# EPS_I2C-Repeater.net
KiCad netlist of a schematic drawn in Altium Designer
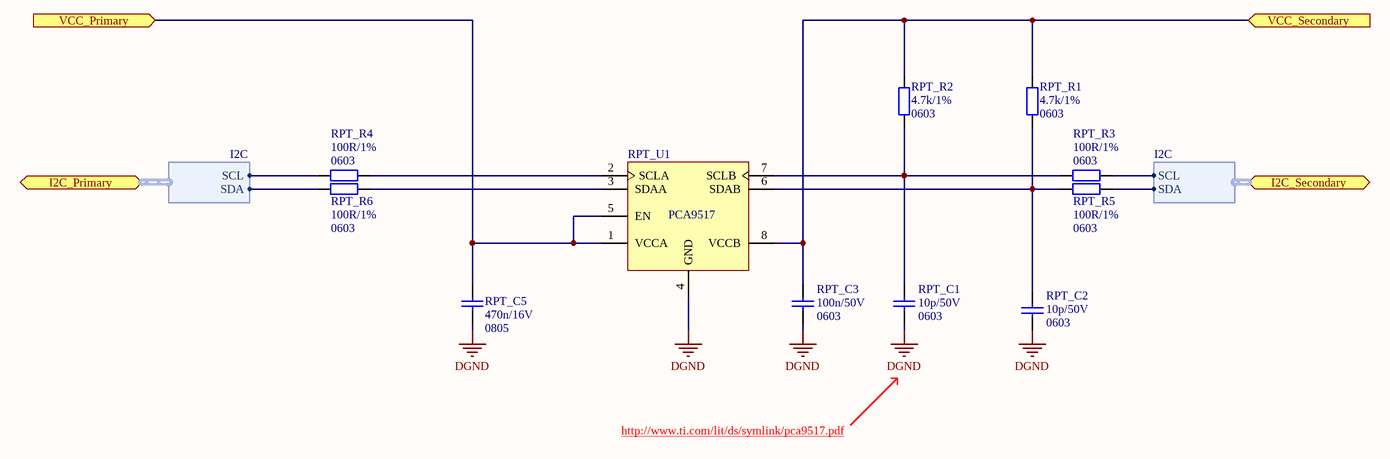
[diagram p0: EPS_I2C-Repeater.SchDoc]

(export (version "E")
  (design (tool "Eeschema 10.0.6"))
  (components
    (comp (ref "RPT_C1")
      (value "10p/50V")
      (footprint "SMD_Capacitor_0603")
      (description "Ceramic Cap Murata Automotive 10p/50V C0G 0603")
      (fields
        (field (name "MANUFACTURER") "Murata")
        (field (name "MANUFACTURERPARTNUMBER") "GCM1885C1H100JA16D")
        (field (name "PACKAGE") "0603")
      )
      (libsource (lib "capacitors") (part "Cer_GCM1885C1H100JA16D"))
    )
    (comp (ref "RPT_C2")
      (value "10p/50V")
      (footprint "SMD_Capacitor_0603")
      (description "Ceramic Cap Murata Automotive 10p/50V C0G 0603")
      (fields
        (field (name "MANUFACTURER") "Murata")
        (field (name "MANUFACTURERPARTNUMBER") "GCM1885C1H100JA16D")
        (field (name "PACKAGE") "0603")
      )
      (libsource (lib "capacitors") (part "Cer_GCM1885C1H100JA16D"))
    )
    (comp (ref "RPT_C3")
      (value "100n/50V")
      (footprint "SMD_Capacitor_0603")
      (description "Ceramic Cap Kemet COTS 100n/50V X7R 0603")
      (fields
        (field (name "MANUFACTURER") "Kemet")
        (field (name "MANUFACTURERPARTNUMBER") "C0603T104K5RALTU")
        (field (name "PACKAGE") "0603")
      )
      (libsource (lib "capacitors") (part "Cer_C0603T104K5RALTU"))
    )
    (comp (ref "RPT_C5")
      (value "470n/16V")
      (footprint "SMD_Capacitor_0805")
      (description "Cap")
      (fields (field (name "PACKAGE") "0805"))
      (libsource (lib "capacitors") (part "Cap"))
    )
    (comp (ref "RPT_R1")
      (value "4.7k/1%")
      (footprint "SMD_Resistor_0603")
      (description "4.7k/1% Vishay CRCW 0603 Resistor. 100mW, 100ppm, 75V.")
      (fields
        (field (name "MANUFACTURER") "Vishay")
        (field (name "MANUFACTUERPARTNUMBER") "CRCW06034K70FKxxxx")
        (field (name "PACKAGE") "0603")
      )
      (libsource (lib "resistors") (part "CRCW06034K70FKxxxx"))
    )
    (comp (ref "RPT_R2")
      (value "4.7k/1%")
      (footprint "SMD_Resistor_0603")
      (description "4.7k/1% Vishay CRCW 0603 Resistor. 100mW, 100ppm, 75V.")
      (fields
        (field (name "MANUFACTURER") "Vishay")
        (field (name "MANUFACTUERPARTNUMBER") "CRCW06034K70FKxxxx")
        (field (name "PACKAGE") "0603")
      )
      (libsource (lib "resistors") (part "CRCW06034K70FKxxxx"))
    )
    (comp (ref "RPT_R3")
      (value "100R/1%")
      (footprint "SMD_Resistor_0603")
      (description "100R/1% Vishay CRCW 0603 Resistor. 100mW, 100ppm, 75V.")
      (fields
        (field (name "MANUFACTURER") "Vishay")
        (field (name "MANUFACTURERPARTNUMBER") "CRCW0603100RFKxxxx")
        (field (name "PACKAGE") "0603")
      )
      (libsource (lib "resistors") (part "CRCW0603100RFKxxxx"))
    )
    (comp (ref "RPT_R4")
      (value "100R/1%")
      (footprint "SMD_Resistor_0603")
      (description "100R/1% Vishay CRCW 0603 Resistor. 100mW, 100ppm, 75V.")
      (fields
        (field (name "MANUFACTURER") "Vishay")
        (field (name "MANUFACTURERPARTNUMBER") "CRCW0603100RFKxxxx")
        (field (name "PACKAGE") "0603")
      )
      (libsource (lib "") (part "CRCW0603100RFKxxxx_1"))
    )
    (comp (ref "RPT_R5")
      (value "100R/1%")
      (footprint "SMD_Resistor_0603")
      (description "100R/1% Vishay CRCW 0603 Resistor. 100mW, 100ppm, 75V.")
      (fields
        (field (name "MANUFACTURER") "Vishay")
        (field (name "MANUFACTURERPARTNUMBER") "CRCW0603100RFKxxxx")
        (field (name "PACKAGE") "0603")
      )
      (libsource (lib "resistors") (part "CRCW0603100RFKxxxx"))
    )
    (comp (ref "RPT_R6")
      (value "100R/1%")
      (footprint "SMD_Resistor_0603")
      (description "100R/1% Vishay CRCW 0603 Resistor. 100mW, 100ppm, 75V.")
      (fields
        (field (name "MANUFACTURER") "Vishay")
        (field (name "MANUFACTURERPARTNUMBER") "CRCW0603100RFKxxxx")
        (field (name "PACKAGE") "0603")
      )
      (libsource (lib "") (part "CRCW0603100RFKxxxx_1"))
    )
    (comp (ref "RPT_U1")
      (value "PCA9517")
      (footprint "TSSOP8_L")
      (description "Level-Translating I2C Bus Repeater")
      (fields
        (field (name "MANUFACTURER") "Texas Instruments")
        (field (name "MANUFACTURERPARTNUMBER") "PCA9517")
      )
      (libsource (lib "microcircuits") (part "PCA9517"))
    )
  )
  (nets
    (net (code "2") (name "/VCC_Primary") (class "Default")
      (node (ref "RPT_C5") (pin "1") (pinfunction "1_1") (pintype "passive"))
      (node (ref "RPT_U1") (pin "1") (pinfunction "VCCA_1") (pintype "passive"))
      (node (ref "RPT_U1") (pin "5") (pinfunction "EN_5") (pintype "passive"))
    )
    (net (code "3") (name "/VCC_Secondary") (class "Default")
      (node (ref "RPT_C3") (pin "2") (pinfunction "2_2") (pintype "passive"))
      (node (ref "RPT_R1") (pin "1") (pinfunction "1_1") (pintype "passive"))
      (node (ref "RPT_R2") (pin "1") (pinfunction "1_1") (pintype "passive"))
      (node (ref "RPT_U1") (pin "8") (pinfunction "VCCB_8") (pintype "passive"))
    )
    (net (code "5") (name "DGND") (class "Default")
      (node (ref "RPT_C1") (pin "2") (pinfunction "2_2") (pintype "passive"))
      (node (ref "RPT_C2") (pin "2") (pinfunction "2_2") (pintype "passive"))
      (node (ref "RPT_C3") (pin "1") (pinfunction "1_1") (pintype "passive"))
      (node (ref "RPT_C5") (pin "2") (pinfunction "2_2") (pintype "passive"))
      (node (ref "RPT_U1") (pin "4") (pinfunction "GND_4") (pintype "passive"))
    )
    (net (code "6") (name "Net-(RPT_U1-SCLA)") (class "Default")
      (node (ref "RPT_R4") (pin "1") (pinfunction "1_1") (pintype "passive"))
      (node (ref "RPT_U1") (pin "2") (pinfunction "SCLA_2") (pintype "passive"))
    )
    (net (code "7") (name "Net-(RPT_U1-SCLB)") (class "Default")
      (node (ref "RPT_C1") (pin "1") (pinfunction "1_1") (pintype "passive"))
      (node (ref "RPT_R2") (pin "2") (pinfunction "2_2") (pintype "passive"))
      (node (ref "RPT_R3") (pin "1") (pinfunction "1_1") (pintype "passive"))
      (node (ref "RPT_U1") (pin "7") (pinfunction "SCLB_7") (pintype "passive"))
    )
    (net (code "8") (name "Net-(RPT_U1-SDAA)") (class "Default")
      (node (ref "RPT_R6") (pin "1") (pinfunction "1_1") (pintype "passive"))
      (node (ref "RPT_U1") (pin "3") (pinfunction "SDAA_3") (pintype "passive"))
    )
    (net (code "9") (name "Net-(RPT_U1-SDAB)") (class "Default")
      (node (ref "RPT_C2") (pin "1") (pinfunction "1_1") (pintype "passive"))
      (node (ref "RPT_R1") (pin "2") (pinfunction "2_2") (pintype "passive"))
      (node (ref "RPT_R5") (pin "1") (pinfunction "1_1") (pintype "passive"))
      (node (ref "RPT_U1") (pin "6") (pinfunction "SDAB_6") (pintype "passive"))
    )
    (net (code "10") (name "unconnected-(RPT_R3-Pad2)") (class "Default")
      (node (ref "RPT_R3") (pin "2") (pinfunction "2_2") (pintype "passive"))
    )
    (net (code "11") (name "unconnected-(RPT_R4-Pad2)") (class "Default")
      (node (ref "RPT_R4") (pin "2") (pinfunction "2_2") (pintype "passive"))
    )
    (net (code "12") (name "unconnected-(RPT_R5-Pad2)") (class "Default")
      (node (ref "RPT_R5") (pin "2") (pinfunction "2_2") (pintype "passive"))
    )
    (net (code "13") (name "unconnected-(RPT_R6-Pad2)") (class "Default")
      (node (ref "RPT_R6") (pin "2") (pinfunction "2_2") (pintype "passive"))
    )
  )
)
